# Octal_SPI_Flash.net
KiCad netlist of a schematic drawn in Altium Designer
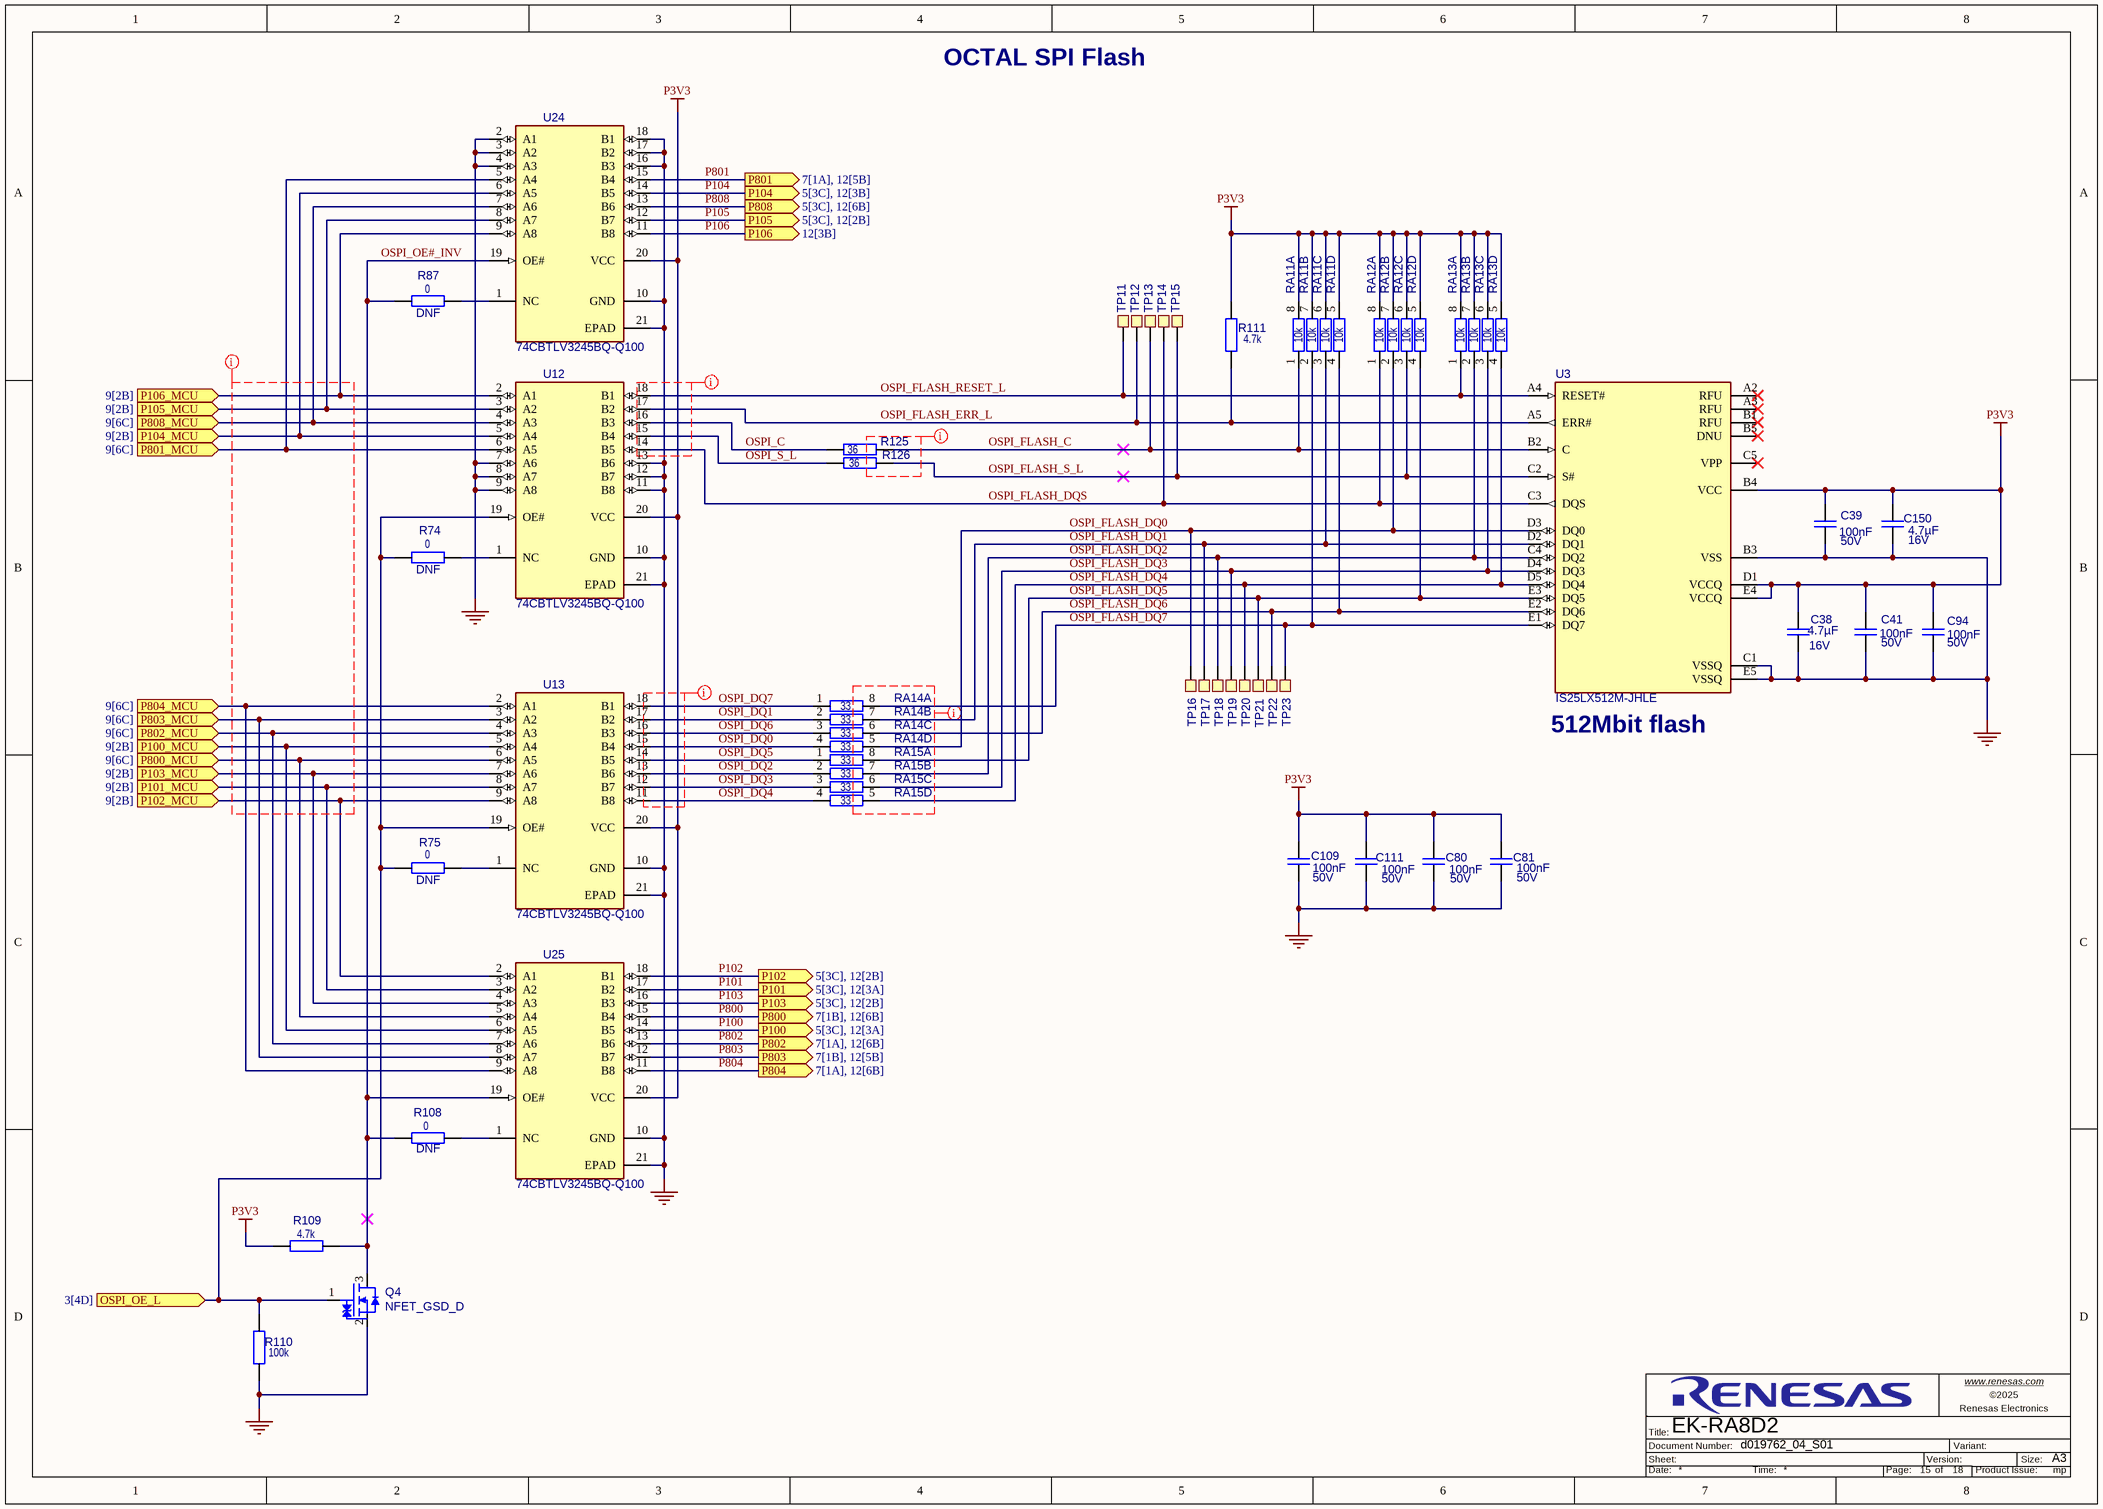
[diagram p0: Octal SPI Flash.SchDoc]

(export (version "E")
  (design (tool "Eeschema 10.0.6"))
  (components
    (comp (ref "C38")
      (value "4.7µF")
      (footprint "C_EIA0402_0p7")
      (description "Capacitor, EIA0402, 4.7u, 16V, X5R")
      (fields
        (field (name "OPERATING VOLTAGE MAX") "16V")
        (field (name "TOLERANCE") "20%")
        (field (name "Comment") "KGM05CR51C475MH")
      )
      (libsource (lib "ek-ra8d2_mp - Customer") (part "Capacitor"))
    )
    (comp (ref "C39")
      (value "100nF")
      (footprint "C_EIA0402_0p55")
      (description "Capacitor,EIA0402,100n,50V,X7R")
      (fields
        (field (name "TOLERANCE") "10%")
        (field (name "OPERATING VOLTAGE MAX") "50V")
        (field (name "Comment") "Capacitor")
      )
      (libsource (lib "ek-ra8d2_mp - Customer") (part "Capacitor"))
    )
    (comp (ref "C41")
      (value "100nF")
      (footprint "C_EIA0402_0p55")
      (description "Capacitor,EIA0402,100n,50V,X7R")
      (fields
        (field (name "TOLERANCE") "10%")
        (field (name "OPERATING VOLTAGE MAX") "50V")
        (field (name "Comment") "Capacitor")
      )
      (libsource (lib "ek-ra8d2_mp - Customer") (part "Capacitor"))
    )
    (comp (ref "C80")
      (value "100nF")
      (footprint "C_EIA0402_0p55")
      (description "Capacitor,EIA0402,100n,50V,X7R")
      (fields
        (field (name "TOLERANCE") "10%")
        (field (name "OPERATING VOLTAGE MAX") "50V")
        (field (name "Comment") "Capacitor")
      )
      (libsource (lib "ek-ra8d2_mp - Customer") (part "Capacitor"))
    )
    (comp (ref "C81")
      (value "100nF")
      (footprint "C_EIA0402_0p55")
      (description "Capacitor,EIA0402,100n,50V,X7R")
      (fields
        (field (name "TOLERANCE") "10%")
        (field (name "OPERATING VOLTAGE MAX") "50V")
        (field (name "Comment") "Capacitor")
      )
      (libsource (lib "ek-ra8d2_mp - Customer") (part "Capacitor"))
    )
    (comp (ref "C94")
      (value "100nF")
      (footprint "C_EIA0402_0p55")
      (description "Capacitor,EIA0402,100n,50V,X7R")
      (fields
        (field (name "TOLERANCE") "10%")
        (field (name "OPERATING VOLTAGE MAX") "50V")
        (field (name "Comment") "Capacitor")
      )
      (libsource (lib "ek-ra8d2_mp - Customer") (part "Capacitor"))
    )
    (comp (ref "C109")
      (value "100nF")
      (footprint "C_EIA0402_0p55")
      (description "Capacitor,EIA0402,100n,50V,X7R")
      (fields
        (field (name "TOLERANCE") "10%")
        (field (name "OPERATING VOLTAGE MAX") "50V")
        (field (name "Comment") "Capacitor")
      )
      (libsource (lib "ek-ra8d2_mp - Customer") (part "Capacitor"))
    )
    (comp (ref "C111")
      (value "100nF")
      (footprint "C_EIA0402_0p55")
      (description "Capacitor,EIA0402,100n,50V,X7R")
      (fields
        (field (name "TOLERANCE") "10%")
        (field (name "OPERATING VOLTAGE MAX") "50V")
        (field (name "Comment") "Capacitor")
      )
      (libsource (lib "ek-ra8d2_mp - Customer") (part "Capacitor"))
    )
    (comp (ref "C150")
      (value "4.7µF")
      (footprint "C_EIA0402_0p7")
      (description "Capacitor, EIA0402, 4.7u, 16V, X5R")
      (fields
        (field (name "OPERATING VOLTAGE MAX") "16V")
        (field (name "TOLERANCE") "20%")
        (field (name "Comment") "KGM05CR51C475MH")
      )
      (libsource (lib "ek-ra8d2_mp - Customer") (part "Capacitor"))
    )
    (comp (ref "Q4")
      (value "NFET_GSD_D")
      (footprint "roh_SOT-416FL_SC-89")
      (description "N-Channel 60V 250mA Small Signal MOSFET")
      (fields (field (name "POWER") "150mW"))
      (libsource (lib "ek-ra8d2_mp - Customer") (part "NFET_GSD_D"))
    )
    (comp (ref "R74")
      (value "0")
      (footprint "R_EIA0402")
      (description "Resistor,EIA0402,0,0.0625W")
      (fields (field (name "POWER") "62.5mW") (field (name "TOLERANCE") "5%") (field (name "DNF") "DNF"))
      (libsource (lib "ek-ra8d2_mp - Customer") (part "Resistor"))
    )
    (comp (ref "R75")
      (value "0")
      (footprint "R_EIA0402")
      (description "Resistor,EIA0402,0,0.0625W")
      (fields (field (name "POWER") "62.5mW") (field (name "TOLERANCE") "5%") (field (name "DNF") "DNF"))
      (libsource (lib "ek-ra8d2_mp - Customer") (part "Resistor"))
    )
    (comp (ref "R87")
      (value "0")
      (footprint "R_EIA0402")
      (description "Resistor,EIA0402,0,0.0625W")
      (fields (field (name "POWER") "62.5mW") (field (name "TOLERANCE") "5%") (field (name "DNF") "DNF"))
      (libsource (lib "ek-ra8d2_mp - Customer") (part "Resistor"))
    )
    (comp (ref "R108")
      (value "0")
      (footprint "R_EIA0402")
      (description "Resistor,EIA0402,0,0.0625W")
      (fields (field (name "POWER") "62.5mW") (field (name "TOLERANCE") "5%") (field (name "DNF") "DNF"))
      (libsource (lib "ek-ra8d2_mp - Customer") (part "Resistor"))
    )
    (comp (ref "R109")
      (value "4.7k")
      (footprint "R_EIA0402")
      (description "Resistor,EIA0402,4.7k,0.0625W")
      (fields (field (name "POWER") "62.5mW") (field (name "TOLERANCE") "1%"))
      (libsource (lib "ek-ra8d2_mp - Customer") (part "Resistor"))
    )
    (comp (ref "R110")
      (value "100k")
      (footprint "R_EIA0402")
      (description "Resistor,EIA0402,100k,0.0625W")
      (fields (field (name "POWER") "62.5mW") (field (name "TOLERANCE") "1%"))
      (libsource (lib "") (part "Resistor_1"))
    )
    (comp (ref "R111")
      (value "4.7k")
      (footprint "R_EIA0402")
      (description "Resistor,EIA0402,4.7k,0.0625W")
      (fields (field (name "POWER") "62.5mW") (field (name "TOLERANCE") "1%"))
      (libsource (lib "") (part "Resistor_1"))
    )
    (comp (ref "R125")
      (value "36")
      (footprint "R_EIA0402")
      (description "Resistor,EIA0402,36,0.0625W")
      (fields (field (name "POWER") "62.5mW") (field (name "TOLERANCE") "1%"))
      (libsource (lib "ek-ra8d2_mp - Customer") (part "Resistor"))
    )
    (comp (ref "R126")
      (value "36")
      (footprint "R_EIA0402")
      (description "Resistor,EIA0402,36,0.0625W")
      (fields (field (name "POWER") "62.5mW") (field (name "TOLERANCE") "1%"))
      (libsource (lib "ek-ra8d2_mp - Customer") (part "Resistor"))
    )
    (comp (ref "RA11")
      (value "10k")
      (footprint "R_Array_EIA0804")
      (description "Resistor Network & Array,0804, 10k,0.0625W")
      (fields (field (name "POWER") "62.5mW") (field (name "TOLERANCE") "1%"))
      (libsource (lib "ek-ra8d2_mp - Customer") (part "Resistor_Array"))
    )
    (comp (ref "RA12")
      (value "10k")
      (footprint "R_Array_EIA0804")
      (description "Resistor Network & Array,0804, 10k,0.0625W")
      (fields (field (name "POWER") "62.5mW") (field (name "TOLERANCE") "1%"))
      (libsource (lib "ek-ra8d2_mp - Customer") (part "Resistor_Array"))
    )
    (comp (ref "RA13")
      (value "10k")
      (footprint "R_Array_EIA0804")
      (description "Resistor Network & Array,0804, 10k,0.0625W")
      (fields (field (name "POWER") "62.5mW") (field (name "TOLERANCE") "1%"))
      (libsource (lib "ek-ra8d2_mp - Customer") (part "Resistor_Array"))
    )
    (comp (ref "RA14")
      (value "33")
      (footprint "R_Array_EIA0804")
      (description "Resistor Network & Array,0804,33,0.0625W")
      (fields (field (name "POWER") "62.5mW") (field (name "TOLERANCE") "1%"))
      (libsource (lib "") (part "Resistor_Array_1"))
    )
    (comp (ref "RA15")
      (value "33")
      (footprint "R_Array_EIA0804")
      (description "Resistor Network & Array,0804,33,0.0625W")
      (fields (field (name "POWER") "62.5mW") (field (name "TOLERANCE") "1%"))
      (libsource (lib "") (part "Resistor_Array_1"))
    )
    (comp (ref "TP11")
      (value "TP_VIA_0p45_0p15")
      (footprint "TP_VIA_0p45_0p15")
      (description "Testpoint,THT,0.45mm PTH")
      (libsource (lib "") (part "tp_1_1"))
    )
    (comp (ref "TP12")
      (value "TP_VIA_0p45_0p15")
      (footprint "TP_VIA_0p45_0p15")
      (description "Testpoint,THT,0.45mm PTH")
      (libsource (lib "") (part "tp_1_1"))
    )
    (comp (ref "TP13")
      (value "TP_VIA_0p45_0p15")
      (footprint "TP_VIA_0p45_0p15")
      (description "Testpoint,THT,0.45mm PTH")
      (libsource (lib "") (part "tp_1_1"))
    )
    (comp (ref "TP14")
      (value "TP_VIA_0p45_0p15")
      (footprint "TP_VIA_0p45_0p15")
      (description "Testpoint,THT,0.45mm PTH")
      (libsource (lib "") (part "tp_1_1"))
    )
    (comp (ref "TP15")
      (value "TP_VIA_0p45_0p15")
      (footprint "TP_VIA_0p45_0p15")
      (description "Testpoint,THT,0.45mm PTH")
      (libsource (lib "") (part "tp_1_1"))
    )
    (comp (ref "TP16")
      (value "TP_VIA_0p45_0p15")
      (footprint "TP_VIA_0p45_0p15")
      (description "Testpoint,THT,0.45mm PTH")
      (libsource (lib "ek-ra8d2_mp - Customer") (part "tp_1"))
    )
    (comp (ref "TP17")
      (value "TP_VIA_0p45_0p15")
      (footprint "TP_VIA_0p45_0p15")
      (description "Testpoint,THT,0.45mm PTH")
      (libsource (lib "ek-ra8d2_mp - Customer") (part "tp_1"))
    )
    (comp (ref "TP18")
      (value "TP_VIA_0p45_0p15")
      (footprint "TP_VIA_0p45_0p15")
      (description "Testpoint,THT,0.45mm PTH")
      (libsource (lib "ek-ra8d2_mp - Customer") (part "tp_1"))
    )
    (comp (ref "TP19")
      (value "TP_VIA_0p45_0p15")
      (footprint "TP_VIA_0p45_0p15")
      (description "Testpoint,THT,0.45mm PTH")
      (libsource (lib "ek-ra8d2_mp - Customer") (part "tp_1"))
    )
    (comp (ref "TP20")
      (value "TP_VIA_0p45_0p15")
      (footprint "TP_VIA_0p45_0p15")
      (description "Testpoint,THT,0.45mm PTH")
      (libsource (lib "ek-ra8d2_mp - Customer") (part "tp_1"))
    )
    (comp (ref "TP21")
      (value "TP_VIA_0p45_0p15")
      (footprint "TP_VIA_0p45_0p15")
      (description "Testpoint,THT,0.45mm PTH")
      (libsource (lib "ek-ra8d2_mp - Customer") (part "tp_1"))
    )
    (comp (ref "TP22")
      (value "TP_VIA_0p45_0p15")
      (footprint "TP_VIA_0p45_0p15")
      (description "Testpoint,THT,0.45mm PTH")
      (libsource (lib "ek-ra8d2_mp - Customer") (part "tp_1"))
    )
    (comp (ref "TP23")
      (value "TP_VIA_0p45_0p15")
      (footprint "TP_VIA_0p45_0p15")
      (description "Testpoint,THT,0.45mm PTH")
      (libsource (lib "ek-ra8d2_mp - Customer") (part "tp_1"))
    )
    (comp (ref "U3")
      (value "IS25LX512M-JHLE")
      (footprint "isi_TFBGA-24_8x6")
      (description "NOR Flash 512Mb, Octal Flash, 3V, 24-ball TFBGA")
      (libsource (lib "ek-ra8d2_mp - Customer") (part "isi_IS25LX512M-JHLE"))
    )
    (comp (ref "U12")
      (value "74CBTLV3245BQ-Q100")
      (footprint "nex_SOT-764-1_DHVQFN20")
      (description "Octal FET Bus Switch, 5 ohm, 0.3ns max delay, DHVQFN20")
      (libsource (lib "ek-ra8d2_mp - Customer") (part "nex_74CBTLV3245-Q100"))
    )
    (comp (ref "U13")
      (value "74CBTLV3245BQ-Q100")
      (footprint "nex_SOT-764-1_DHVQFN20")
      (description "Octal FET Bus Switch, 5 ohm, 0.3ns max delay, DHVQFN20")
      (libsource (lib "ek-ra8d2_mp - Customer") (part "nex_74CBTLV3245-Q100"))
    )
    (comp (ref "U24")
      (value "74CBTLV3245BQ-Q100")
      (footprint "nex_SOT-764-1_DHVQFN20")
      (description "Octal FET Bus Switch, 5 ohm, 0.3ns max delay, DHVQFN20")
      (libsource (lib "ek-ra8d2_mp - Customer") (part "nex_74CBTLV3245-Q100"))
    )
    (comp (ref "U25")
      (value "74CBTLV3245BQ-Q100")
      (footprint "nex_SOT-764-1_DHVQFN20")
      (description "Octal FET Bus Switch, 5 ohm, 0.3ns max delay, DHVQFN20")
      (libsource (lib "ek-ra8d2_mp - Customer") (part "nex_74CBTLV3245-Q100"))
    )
  )
  (nets
    (net (code "1") (name "/OSPI_C") (class "Default")
      (node (ref "R125") (pin "1") (pinfunction "1_1") (pintype "passive"))
      (node (ref "U12") (pin "16") (pinfunction "B3_16") (pintype "bidirectional"))
    )
    (net (code "2") (name "/OSPI_DQ0") (class "Default")
      (node (ref "RA14") (pin "4") (pinfunction "4_4") (pintype "passive"))
      (node (ref "U13") (pin "15") (pinfunction "B4_15") (pintype "bidirectional"))
    )
    (net (code "3") (name "/OSPI_DQ1") (class "Default")
      (node (ref "RA14") (pin "2") (pinfunction "2_2") (pintype "passive"))
      (node (ref "U13") (pin "17") (pinfunction "B2_17") (pintype "bidirectional"))
    )
    (net (code "4") (name "/OSPI_DQ2") (class "Default")
      (node (ref "RA15") (pin "2") (pinfunction "2_2") (pintype "passive"))
      (node (ref "U13") (pin "13") (pinfunction "B6_13") (pintype "bidirectional"))
    )
    (net (code "5") (name "/OSPI_DQ3") (class "Default")
      (node (ref "RA15") (pin "3") (pinfunction "3_3") (pintype "passive"))
      (node (ref "U13") (pin "12") (pinfunction "B7_12") (pintype "bidirectional"))
    )
    (net (code "6") (name "/OSPI_DQ4") (class "Default")
      (node (ref "RA15") (pin "4") (pinfunction "4_4") (pintype "passive"))
      (node (ref "U13") (pin "11") (pinfunction "B8_11") (pintype "bidirectional"))
    )
    (net (code "7") (name "/OSPI_DQ5") (class "Default")
      (node (ref "RA15") (pin "1") (pinfunction "1_1") (pintype "passive"))
      (node (ref "U13") (pin "14") (pinfunction "B5_14") (pintype "bidirectional"))
    )
    (net (code "8") (name "/OSPI_DQ6") (class "Default")
      (node (ref "RA14") (pin "3") (pinfunction "3_3") (pintype "passive"))
      (node (ref "U13") (pin "16") (pinfunction "B3_16") (pintype "bidirectional"))
    )
    (net (code "9") (name "/OSPI_DQ7") (class "Default")
      (node (ref "RA14") (pin "1") (pinfunction "1_1") (pintype "passive"))
      (node (ref "U13") (pin "18") (pinfunction "B1_18") (pintype "bidirectional"))
    )
    (net (code "10") (name "/OSPI_FLASH_C") (class "Default")
      (node (ref "R125") (pin "2") (pinfunction "2_2") (pintype "passive"))
      (node (ref "RA11") (pin "1") (pinfunction "1_1") (pintype "passive"))
      (node (ref "TP13") (pin "1") (pinfunction "1_1") (pintype "passive"))
      (node (ref "U3") (pin "B2") (pinfunction "C_B2") (pintype "input"))
    )
    (net (code "11") (name "/OSPI_FLASH_DQ0") (class "Default")
      (node (ref "RA12") (pin "2") (pinfunction "2_2") (pintype "passive"))
      (node (ref "RA14") (pin "5") (pinfunction "5_5") (pintype "passive"))
      (node (ref "TP16") (pin "1") (pinfunction "1_1") (pintype "passive"))
      (node (ref "U3") (pin "D3") (pinfunction "DQ0_D3") (pintype "bidirectional"))
    )
    (net (code "12") (name "/OSPI_FLASH_DQ1") (class "Default")
      (node (ref "RA11") (pin "3") (pinfunction "3_3") (pintype "passive"))
      (node (ref "RA14") (pin "7") (pinfunction "7_7") (pintype "passive"))
      (node (ref "TP17") (pin "1") (pinfunction "1_1") (pintype "passive"))
      (node (ref "U3") (pin "D2") (pinfunction "DQ1_D2") (pintype "bidirectional"))
    )
    (net (code "13") (name "/OSPI_FLASH_DQ2") (class "Default")
      (node (ref "RA13") (pin "2") (pinfunction "2_2") (pintype "passive"))
      (node (ref "RA15") (pin "7") (pinfunction "7_7") (pintype "passive"))
      (node (ref "TP18") (pin "1") (pinfunction "1_1") (pintype "passive"))
      (node (ref "U3") (pin "C4") (pinfunction "DQ2_C4") (pintype "bidirectional"))
    )
    (net (code "14") (name "/OSPI_FLASH_DQ3") (class "Default")
      (node (ref "RA13") (pin "3") (pinfunction "3_3") (pintype "passive"))
      (node (ref "RA15") (pin "6") (pinfunction "6_6") (pintype "passive"))
      (node (ref "TP19") (pin "1") (pinfunction "1_1") (pintype "passive"))
      (node (ref "U3") (pin "D4") (pinfunction "DQ3_D4") (pintype "bidirectional"))
    )
    (net (code "15") (name "/OSPI_FLASH_DQ4") (class "Default")
      (node (ref "RA13") (pin "4") (pinfunction "4_4") (pintype "passive"))
      (node (ref "RA15") (pin "5") (pinfunction "5_5") (pintype "passive"))
      (node (ref "TP20") (pin "1") (pinfunction "1_1") (pintype "passive"))
      (node (ref "U3") (pin "D5") (pinfunction "DQ4_D5") (pintype "bidirectional"))
    )
    (net (code "16") (name "/OSPI_FLASH_DQ5") (class "Default")
      (node (ref "RA12") (pin "4") (pinfunction "4_4") (pintype "passive"))
      (node (ref "RA15") (pin "8") (pinfunction "8_8") (pintype "passive"))
      (node (ref "TP21") (pin "1") (pinfunction "1_1") (pintype "passive"))
      (node (ref "U3") (pin "E3") (pinfunction "DQ5_E3") (pintype "bidirectional"))
    )
    (net (code "17") (name "/OSPI_FLASH_DQ6") (class "Default")
      (node (ref "RA11") (pin "4") (pinfunction "4_4") (pintype "passive"))
      (node (ref "RA14") (pin "6") (pinfunction "6_6") (pintype "passive"))
      (node (ref "TP22") (pin "1") (pinfunction "1_1") (pintype "passive"))
      (node (ref "U3") (pin "E2") (pinfunction "DQ6_E2") (pintype "bidirectional"))
    )
    (net (code "18") (name "/OSPI_FLASH_DQ7") (class "Default")
      (node (ref "RA11") (pin "2") (pinfunction "2_2") (pintype "passive"))
      (node (ref "RA14") (pin "8") (pinfunction "8_8") (pintype "passive"))
      (node (ref "TP23") (pin "1") (pinfunction "1_1") (pintype "passive"))
      (node (ref "U3") (pin "E1") (pinfunction "DQ7_E1") (pintype "bidirectional"))
    )
    (net (code "19") (name "/OSPI_FLASH_DQS") (class "Default")
      (node (ref "RA12") (pin "1") (pinfunction "1_1") (pintype "passive"))
      (node (ref "TP14") (pin "1") (pinfunction "1_1") (pintype "passive"))
      (node (ref "U12") (pin "14") (pinfunction "B5_14") (pintype "bidirectional"))
      (node (ref "U3") (pin "C3") (pinfunction "DQS_C3") (pintype "output"))
    )
    (net (code "20") (name "/OSPI_FLASH_ERR_L") (class "Default")
      (node (ref "R111") (pin "1") (pinfunction "1_1") (pintype "passive"))
      (node (ref "TP12") (pin "1") (pinfunction "1_1") (pintype "passive"))
      (node (ref "U12") (pin "17") (pinfunction "B2_17") (pintype "bidirectional"))
      (node (ref "U3") (pin "A5") (pinfunction "ERR#_A5") (pintype "output"))
    )
    (net (code "21") (name "/OSPI_FLASH_RESET_L") (class "Default")
      (node (ref "RA13") (pin "1") (pinfunction "1_1") (pintype "passive"))
      (node (ref "TP11") (pin "1") (pinfunction "1_1") (pintype "passive"))
      (node (ref "U12") (pin "18") (pinfunction "B1_18") (pintype "bidirectional"))
      (node (ref "U3") (pin "A4") (pinfunction "RESET#_A4") (pintype "input"))
    )
    (net (code "22") (name "/OSPI_FLASH_S_L") (class "Default")
      (node (ref "R126") (pin "2") (pinfunction "2_2") (pintype "passive"))
      (node (ref "RA12") (pin "3") (pinfunction "3_3") (pintype "passive"))
      (node (ref "TP15") (pin "1") (pinfunction "1_1") (pintype "passive"))
      (node (ref "U3") (pin "C2") (pinfunction "S#_C2") (pintype "input"))
    )
    (net (code "23") (name "/OSPI_OE#_INV") (class "Default")
      (node (ref "Q4") (pin "3") (pinfunction "Drain_3") (pintype "passive"))
      (node (ref "R108") (pin "1") (pinfunction "1_1") (pintype "passive"))
      (node (ref "R109") (pin "2") (pinfunction "2_2") (pintype "passive"))
      (node (ref "R87") (pin "1") (pinfunction "1_1") (pintype "passive"))
      (node (ref "U24") (pin "19") (pinfunction "OE#_19") (pintype "input"))
      (node (ref "U25") (pin "19") (pinfunction "OE#_19") (pintype "input"))
    )
    (net (code "24") (name "/OSPI_OE_L") (class "Default")
      (node (ref "Q4") (pin "1") (pinfunction "Gate_1") (pintype "passive"))
      (node (ref "R110") (pin "2") (pinfunction "2_2") (pintype "passive"))
      (node (ref "R74") (pin "1") (pinfunction "1_1") (pintype "passive"))
      (node (ref "R75") (pin "1") (pinfunction "1_1") (pintype "passive"))
      (node (ref "U12") (pin "19") (pinfunction "OE#_19") (pintype "input"))
      (node (ref "U13") (pin "19") (pinfunction "OE#_19") (pintype "input"))
    )
    (net (code "25") (name "/OSPI_S_L") (class "Default")
      (node (ref "R126") (pin "1") (pinfunction "1_1") (pintype "passive"))
      (node (ref "U12") (pin "15") (pinfunction "B4_15") (pintype "bidirectional"))
    )
    (net (code "26") (name "/P100") (class "Default")
      (node (ref "U25") (pin "14") (pinfunction "B5_14") (pintype "bidirectional"))
    )
    (net (code "27") (name "/P100_MCU") (class "Default")
      (node (ref "U13") (pin "5") (pinfunction "A4_5") (pintype "bidirectional"))
      (node (ref "U25") (pin "6") (pinfunction "A5_6") (pintype "bidirectional"))
    )
    (net (code "28") (name "/P101") (class "Default")
      (node (ref "U25") (pin "17") (pinfunction "B2_17") (pintype "bidirectional"))
    )
    (net (code "29") (name "/P101_MCU") (class "Default")
      (node (ref "U13") (pin "8") (pinfunction "A7_8") (pintype "bidirectional"))
      (node (ref "U25") (pin "3") (pinfunction "A2_3") (pintype "bidirectional"))
    )
    (net (code "30") (name "/P102") (class "Default")
      (node (ref "U25") (pin "18") (pinfunction "B1_18") (pintype "bidirectional"))
    )
    (net (code "31") (name "/P102_MCU") (class "Default")
      (node (ref "U13") (pin "9") (pinfunction "A8_9") (pintype "bidirectional"))
      (node (ref "U25") (pin "2") (pinfunction "A1_2") (pintype "bidirectional"))
    )
    (net (code "32") (name "/P103") (class "Default")
      (node (ref "U25") (pin "16") (pinfunction "B3_16") (pintype "bidirectional"))
    )
    (net (code "33") (name "/P103_MCU") (class "Default")
      (node (ref "U13") (pin "7") (pinfunction "A6_7") (pintype "bidirectional"))
      (node (ref "U25") (pin "4") (pinfunction "A3_4") (pintype "bidirectional"))
    )
    (net (code "34") (name "/P104") (class "Default")
      (node (ref "U24") (pin "14") (pinfunction "B5_14") (pintype "bidirectional"))
    )
    (net (code "35") (name "/P104_MCU") (class "Default")
      (node (ref "U12") (pin "5") (pinfunction "A4_5") (pintype "bidirectional"))
      (node (ref "U24") (pin "6") (pinfunction "A5_6") (pintype "bidirectional"))
    )
    (net (code "36") (name "/P105") (class "Default")
      (node (ref "U24") (pin "12") (pinfunction "B7_12") (pintype "bidirectional"))
    )
    (net (code "37") (name "/P105_MCU") (class "Default")
      (node (ref "U12") (pin "3") (pinfunction "A2_3") (pintype "bidirectional"))
      (node (ref "U24") (pin "8") (pinfunction "A7_8") (pintype "bidirectional"))
    )
    (net (code "38") (name "/P106") (class "Default")
      (node (ref "U24") (pin "11") (pinfunction "B8_11") (pintype "bidirectional"))
    )
    (net (code "39") (name "/P106_MCU") (class "Default")
      (node (ref "U12") (pin "2") (pinfunction "A1_2") (pintype "bidirectional"))
      (node (ref "U24") (pin "9") (pinfunction "A8_9") (pintype "bidirectional"))
    )
    (net (code "40") (name "/P800") (class "Default")
      (node (ref "U25") (pin "15") (pinfunction "B4_15") (pintype "bidirectional"))
    )
    (net (code "41") (name "/P800_MCU") (class "Default")
      (node (ref "U13") (pin "6") (pinfunction "A5_6") (pintype "bidirectional"))
      (node (ref "U25") (pin "5") (pinfunction "A4_5") (pintype "bidirectional"))
    )
    (net (code "42") (name "/P801") (class "Default")
      (node (ref "U24") (pin "15") (pinfunction "B4_15") (pintype "bidirectional"))
    )
    (net (code "43") (name "/P801_MCU") (class "Default")
      (node (ref "U12") (pin "6") (pinfunction "A5_6") (pintype "bidirectional"))
      (node (ref "U24") (pin "5") (pinfunction "A4_5") (pintype "bidirectional"))
    )
    (net (code "44") (name "/P802") (class "Default")
      (node (ref "U25") (pin "13") (pinfunction "B6_13") (pintype "bidirectional"))
    )
    (net (code "45") (name "/P802_MCU") (class "Default")
      (node (ref "U13") (pin "4") (pinfunction "A3_4") (pintype "bidirectional"))
      (node (ref "U25") (pin "7") (pinfunction "A6_7") (pintype "bidirectional"))
    )
    (net (code "46") (name "/P803") (class "Default")
      (node (ref "U25") (pin "12") (pinfunction "B7_12") (pintype "bidirectional"))
    )
    (net (code "47") (name "/P803_MCU") (class "Default")
      (node (ref "U13") (pin "3") (pinfunction "A2_3") (pintype "bidirectional"))
      (node (ref "U25") (pin "8") (pinfunction "A7_8") (pintype "bidirectional"))
    )
    (net (code "48") (name "/P804") (class "Default")
      (node (ref "U25") (pin "11") (pinfunction "B8_11") (pintype "bidirectional"))
    )
    (net (code "49") (name "/P804_MCU") (class "Default")
      (node (ref "U13") (pin "2") (pinfunction "A1_2") (pintype "bidirectional"))
      (node (ref "U25") (pin "9") (pinfunction "A8_9") (pintype "bidirectional"))
    )
    (net (code "50") (name "/P808") (class "Default")
      (node (ref "U24") (pin "13") (pinfunction "B6_13") (pintype "bidirectional"))
    )
    (net (code "51") (name "/P808_MCU") (class "Default")
      (node (ref "U12") (pin "4") (pinfunction "A3_4") (pintype "bidirectional"))
      (node (ref "U24") (pin "7") (pinfunction "A6_7") (pintype "bidirectional"))
    )
    (net (code "52") (name "GND") (class "Default")
      (node (ref "C109") (pin "2") (pinfunction "2_2") (pintype "passive"))
      (node (ref "C111") (pin "2") (pinfunction "2_2") (pintype "passive"))
      (node (ref "C150") (pin "2") (pinfunction "2_2") (pintype "passive"))
      (node (ref "C38") (pin "2") (pinfunction "2_2") (pintype "passive"))
      (node (ref "C39") (pin "2") (pinfunction "2_2") (pintype "passive"))
      (node (ref "C41") (pin "2") (pinfunction "2_2") (pintype "passive"))
      (node (ref "C80") (pin "2") (pinfunction "2_2") (pintype "passive"))
      (node (ref "C81") (pin "2") (pinfunction "2_2") (pintype "passive"))
      (node (ref "C94") (pin "2") (pinfunction "2_2") (pintype "passive"))
      (node (ref "Q4") (pin "2") (pinfunction "Source_2") (pintype "passive"))
      (node (ref "R110") (pin "1") (pinfunction "1_1") (pintype "passive"))
      (node (ref "U12") (pin "10") (pinfunction "GND_10") (pintype "power_in"))
      (node (ref "U12") (pin "11") (pinfunction "B8_11") (pintype "bidirectional"))
      (node (ref "U12") (pin "12") (pinfunction "B7_12") (pintype "bidirectional"))
      (node (ref "U12") (pin "13") (pinfunction "B6_13") (pintype "bidirectional"))
      (node (ref "U12") (pin "21") (pinfunction "EPAD_21") (pintype "power_in"))
      (node (ref "U12") (pin "7") (pinfunction "A6_7") (pintype "bidirectional"))
      (node (ref "U12") (pin "8") (pinfunction "A7_8") (pintype "bidirectional"))
      (node (ref "U12") (pin "9") (pinfunction "A8_9") (pintype "bidirectional"))
      (node (ref "U13") (pin "10") (pinfunction "GND_10") (pintype "power_in"))
      (node (ref "U13") (pin "21") (pinfunction "EPAD_21") (pintype "power_in"))
      (node (ref "U24") (pin "10") (pinfunction "GND_10") (pintype "power_in"))
      (node (ref "U24") (pin "16") (pinfunction "B3_16") (pintype "bidirectional"))
      (node (ref "U24") (pin "17") (pinfunction "B2_17") (pintype "bidirectional"))
      (node (ref "U24") (pin "18") (pinfunction "B1_18") (pintype "bidirectional"))
      (node (ref "U24") (pin "2") (pinfunction "A1_2") (pintype "bidirectional"))
      (node (ref "U24") (pin "21") (pinfunction "EPAD_21") (pintype "power_in"))
      (node (ref "U24") (pin "3") (pinfunction "A2_3") (pintype "bidirectional"))
      (node (ref "U24") (pin "4") (pinfunction "A3_4") (pintype "bidirectional"))
      (node (ref "U25") (pin "10") (pinfunction "GND_10") (pintype "power_in"))
      (node (ref "U25") (pin "21") (pinfunction "EPAD_21") (pintype "power_in"))
      (node (ref "U3") (pin "B3") (pinfunction "VSS_B3") (pintype "power_in"))
      (node (ref "U3") (pin "C1") (pinfunction "VSSQ_C1") (pintype "power_in"))
      (node (ref "U3") (pin "E5") (pinfunction "VSSQ_E5") (pintype "power_in"))
    )
    (net (code "53") (name "Net-(U12-NC)") (class "Default")
      (node (ref "R74") (pin "2") (pinfunction "2_2") (pintype "passive"))
      (node (ref "U12") (pin "1") (pinfunction "NC_1") (pintype "passive"))
    )
    (net (code "54") (name "Net-(U13-NC)") (class "Default")
      (node (ref "R75") (pin "2") (pinfunction "2_2") (pintype "passive"))
      (node (ref "U13") (pin "1") (pinfunction "NC_1") (pintype "passive"))
    )
    (net (code "55") (name "Net-(U24-NC)") (class "Default")
      (node (ref "R87") (pin "2") (pinfunction "2_2") (pintype "passive"))
      (node (ref "U24") (pin "1") (pinfunction "NC_1") (pintype "passive"))
    )
    (net (code "56") (name "Net-(U25-NC)") (class "Default")
      (node (ref "R108") (pin "2") (pinfunction "2_2") (pintype "passive"))
      (node (ref "U25") (pin "1") (pinfunction "NC_1") (pintype "passive"))
    )
    (net (code "57") (name "P3V3") (class "Default")
      (node (ref "C109") (pin "1") (pinfunction "1_1") (pintype "passive"))
      (node (ref "C111") (pin "1") (pinfunction "1_1") (pintype "passive"))
      (node (ref "C150") (pin "1") (pinfunction "1_1") (pintype "passive"))
      (node (ref "C38") (pin "1") (pinfunction "1_1") (pintype "passive"))
      (node (ref "C39") (pin "1") (pinfunction "1_1") (pintype "passive"))
      (node (ref "C41") (pin "1") (pinfunction "1_1") (pintype "passive"))
      (node (ref "C80") (pin "1") (pinfunction "1_1") (pintype "passive"))
      (node (ref "C81") (pin "1") (pinfunction "1_1") (pintype "passive"))
      (node (ref "C94") (pin "1") (pinfunction "1_1") (pintype "passive"))
      (node (ref "R109") (pin "1") (pinfunction "1_1") (pintype "passive"))
      (node (ref "R111") (pin "2") (pinfunction "2_2") (pintype "passive"))
      (node (ref "RA11") (pin "5") (pinfunction "5_5") (pintype "passive"))
      (node (ref "RA11") (pin "6") (pinfunction "6_6") (pintype "passive"))
      (node (ref "RA11") (pin "7") (pinfunction "7_7") (pintype "passive"))
      (node (ref "RA11") (pin "8") (pinfunction "8_8") (pintype "passive"))
      (node (ref "RA12") (pin "5") (pinfunction "5_5") (pintype "passive"))
      (node (ref "RA12") (pin "6") (pinfunction "6_6") (pintype "passive"))
      (node (ref "RA12") (pin "7") (pinfunction "7_7") (pintype "passive"))
      (node (ref "RA12") (pin "8") (pinfunction "8_8") (pintype "passive"))
      (node (ref "RA13") (pin "5") (pinfunction "5_5") (pintype "passive"))
      (node (ref "RA13") (pin "6") (pinfunction "6_6") (pintype "passive"))
      (node (ref "RA13") (pin "7") (pinfunction "7_7") (pintype "passive"))
      (node (ref "RA13") (pin "8") (pinfunction "8_8") (pintype "passive"))
      (node (ref "U12") (pin "20") (pinfunction "VCC_20") (pintype "power_in"))
      (node (ref "U13") (pin "20") (pinfunction "VCC_20") (pintype "power_in"))
      (node (ref "U24") (pin "20") (pinfunction "VCC_20") (pintype "power_in"))
      (node (ref "U25") (pin "20") (pinfunction "VCC_20") (pintype "power_in"))
      (node (ref "U3") (pin "B4") (pinfunction "VCC_B4") (pintype "power_in"))
      (node (ref "U3") (pin "D1") (pinfunction "VCCQ_D1") (pintype "power_in"))
      (node (ref "U3") (pin "E4") (pinfunction "VCCQ_E4") (pintype "power_in"))
    )
    (net (code "58") (name "unconnected-(U3-DNU-PadB5)") (class "Default")
      (node (ref "U3") (pin "B5") (pinfunction "DNU_B5") (pintype "passive+no_connect"))
    )
    (net (code "59") (name "unconnected-(U3-RFU-PadA2)") (class "Default")
      (node (ref "U3") (pin "A2") (pinfunction "RFU_A2") (pintype "passive+no_connect"))
    )
    (net (code "60") (name "unconnected-(U3-RFU-PadA3)") (class "Default")
      (node (ref "U3") (pin "A3") (pinfunction "RFU_A3") (pintype "passive+no_connect"))
    )
    (net (code "61") (name "unconnected-(U3-RFU-PadB1)") (class "Default")
      (node (ref "U3") (pin "B1") (pinfunction "RFU_B1") (pintype "passive+no_connect"))
    )
    (net (code "62") (name "unconnected-(U3-VPP-PadC5)") (class "Default")
      (node (ref "U3") (pin "C5") (pinfunction "VPP_C5") (pintype "power_in+no_connect"))
    )
  )
)
